# untitled.net
KiCad netlist of a schematic drawn in EAGLE
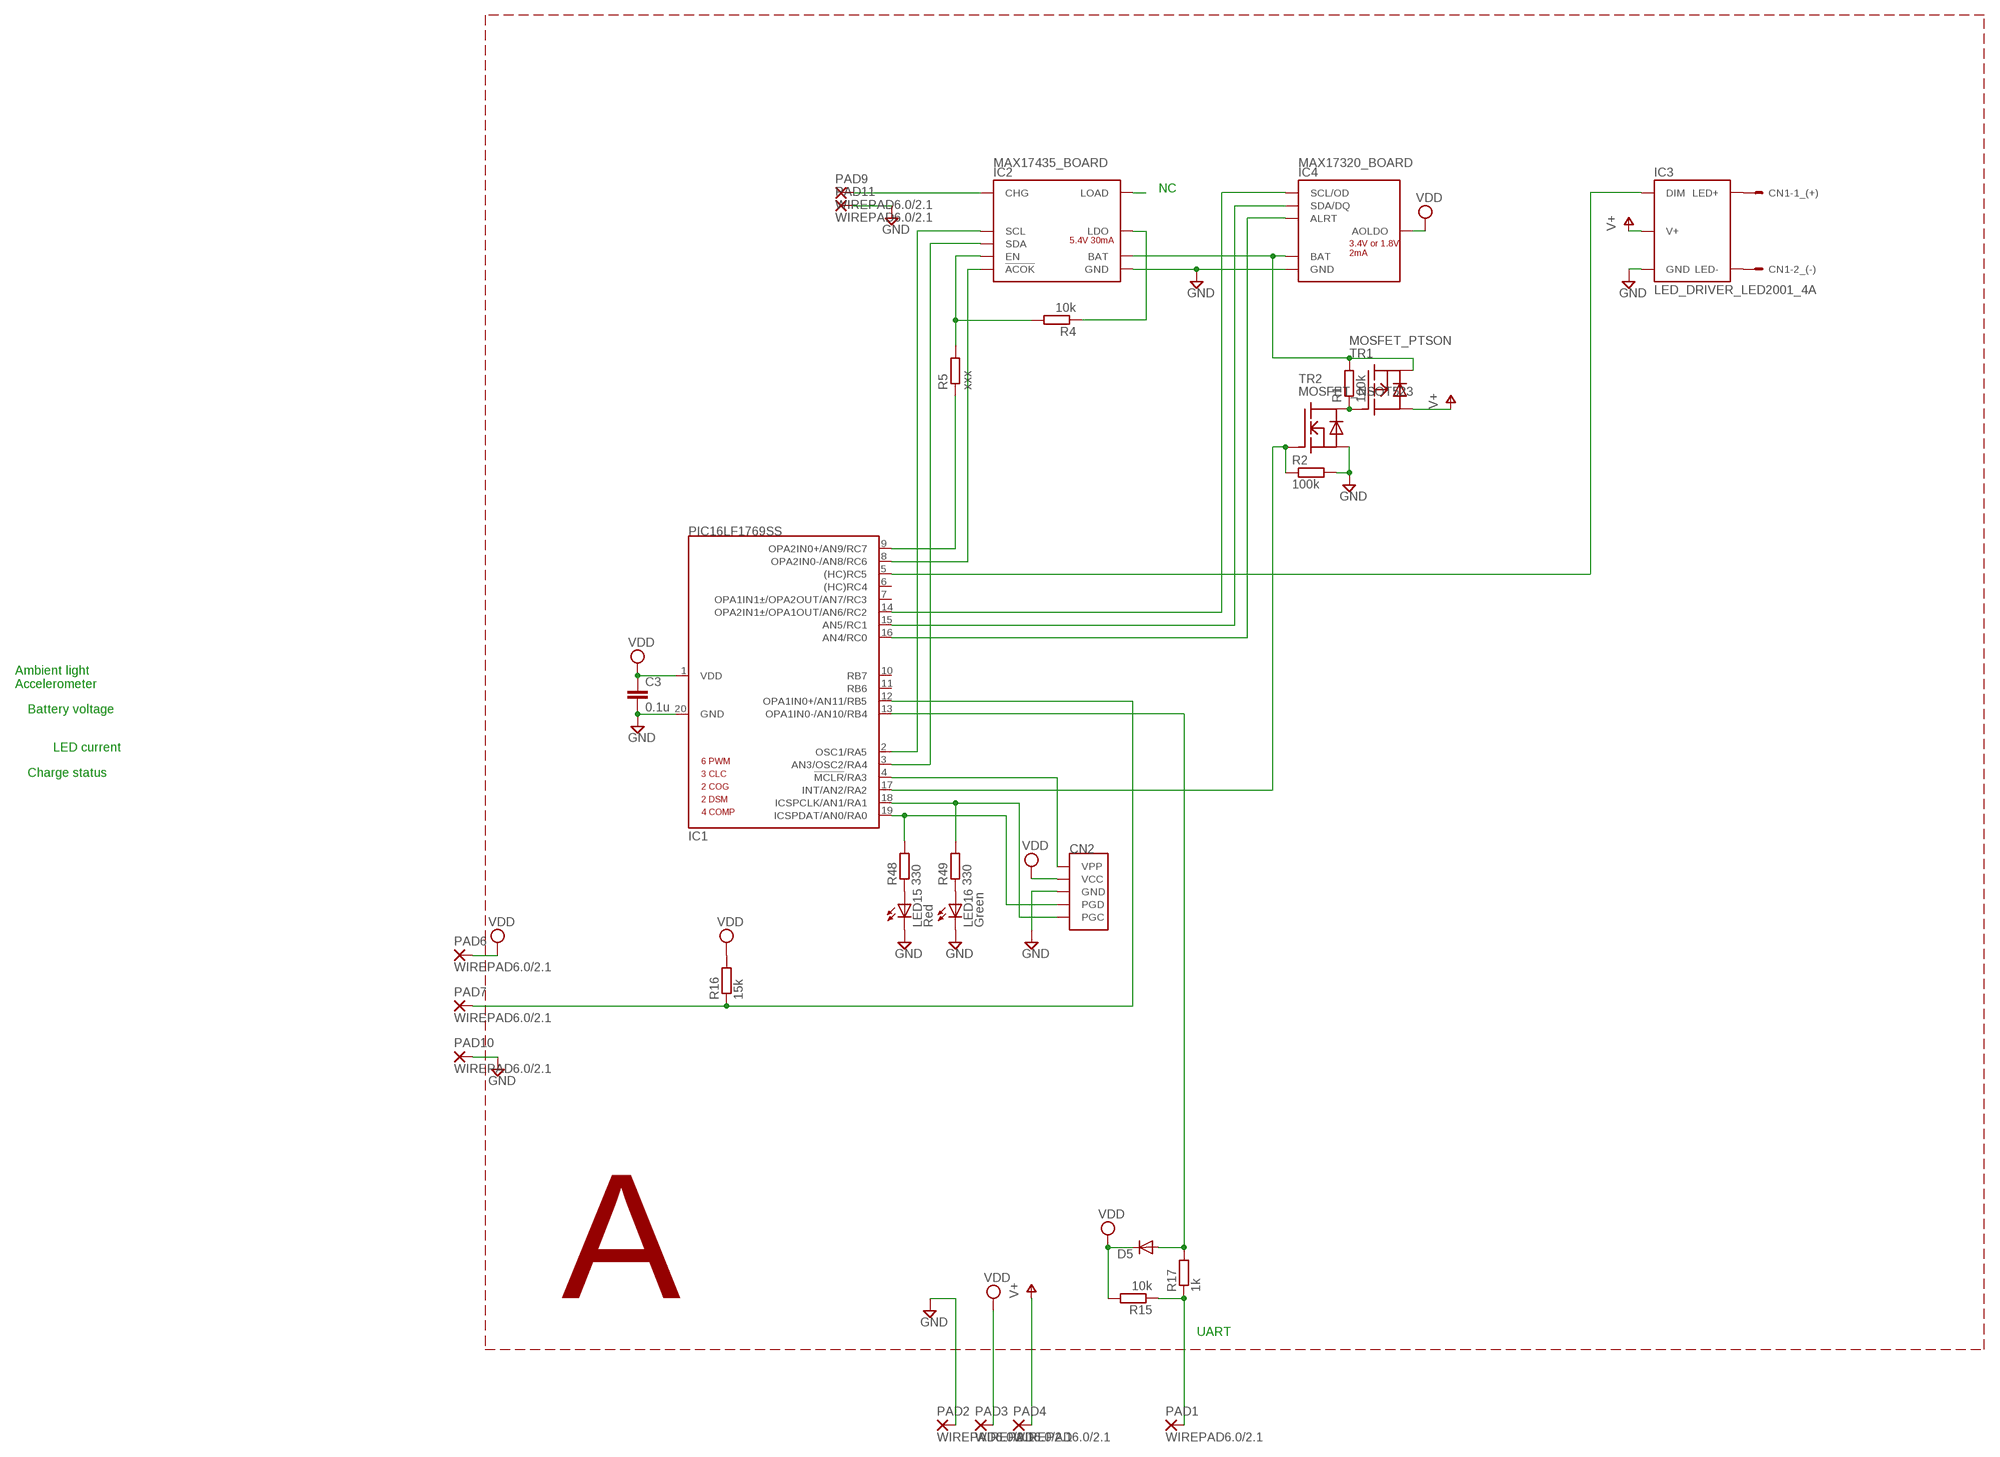
[diagram p0: schematic, sheet 1]

(export (version "E")
  (design (tool "Eeschema 10.0.6"))
  (components
    (comp (ref "C3")
      (value "0.1u")
      (footprint "eagle-import:C0402")
      (libsource (lib "eagle-import") (part "C-EUC0402"))
    )
    (comp (ref "CN1")
      (value "2P_(POWER)XH_S")
      (footprint "eagle-import:XH-2_S")
      (libsource (lib "eagle-import") (part "2P_(POWER)XH_S"))
    )
    (comp (ref "CN2")
      (value "ICSPEDGE")
      (footprint "eagle-import:MINI-ICSP_EDGE")
      (libsource (lib "eagle-import") (part "ICSPEDGE"))
    )
    (comp (ref "D5")
      (value "DIODE-VMN2")
      (footprint "eagle-import:VMN2")
      (libsource (lib "eagle-import") (part "DIODE-VMN2"))
    )
    (comp (ref "IC1")
      (value "PIC16LF1769SS")
      (footprint "eagle-import:SSOP20")
      (libsource (lib "eagle-import") (part "PIC16F1769SS"))
    )
    (comp (ref "IC2")
      (value "MAX17435_BOARD")
      (footprint "eagle-import:MAX17435_BOARD")
      (libsource (lib "eagle-import") (part "MAX17435_BOARD"))
    )
    (comp (ref "IC3")
      (value "LED_DRIVER_LED2001_4A")
      (footprint "eagle-import:LED_DRIVER_LED2001_4A")
      (libsource (lib "eagle-import") (part "LED_DRIVER_LED2001_4A"))
    )
    (comp (ref "IC4")
      (value "MAX17320_BOARD")
      (footprint "eagle-import:MAX17320_BOARD")
      (libsource (lib "eagle-import") (part "MAX17320_BOARD"))
    )
    (comp (ref "LED15")
      (value "Red")
      (footprint "eagle-import:CHIP-LED1606(SIDE)")
      (libsource (lib "eagle-import") (part "LEDCHIPLED_1606(SIDE)"))
    )
    (comp (ref "LED16")
      (value "Green")
      (footprint "eagle-import:CHIP-LED1606(SIDE)")
      (libsource (lib "eagle-import") (part "LEDCHIPLED_1606(SIDE)"))
    )
    (comp (ref "PAD1")
      (value "WIREPAD6.0/2.1")
      (footprint "eagle-import:6.0_2.1")
      (libsource (lib "eagle-import") (part "WIREPAD6.0/2.1"))
    )
    (comp (ref "PAD2")
      (value "WIREPAD6.0/2.1")
      (footprint "eagle-import:6.0_2.1")
      (libsource (lib "eagle-import") (part "WIREPAD6.0/2.1"))
    )
    (comp (ref "PAD3")
      (value "WIREPAD6.0/2.1")
      (footprint "eagle-import:6.0_2.1")
      (libsource (lib "eagle-import") (part "WIREPAD6.0/2.1"))
    )
    (comp (ref "PAD4")
      (value "WIREPAD6.0/2.1")
      (footprint "eagle-import:6.0_2.1")
      (libsource (lib "eagle-import") (part "WIREPAD6.0/2.1"))
    )
    (comp (ref "PAD6")
      (value "WIREPAD6.0/2.1")
      (footprint "eagle-import:6.0_2.1")
      (libsource (lib "eagle-import") (part "WIREPAD6.0/2.1"))
    )
    (comp (ref "PAD7")
      (value "WIREPAD6.0/2.1")
      (footprint "eagle-import:6.0_2.1")
      (libsource (lib "eagle-import") (part "WIREPAD6.0/2.1"))
    )
    (comp (ref "PAD9")
      (value "WIREPAD6.0/2.1")
      (footprint "eagle-import:6.0_2.1")
      (libsource (lib "eagle-import") (part "WIREPAD6.0/2.1"))
    )
    (comp (ref "PAD10")
      (value "WIREPAD6.0/2.1")
      (footprint "eagle-import:6.0_2.1")
      (libsource (lib "eagle-import") (part "WIREPAD6.0/2.1"))
    )
    (comp (ref "PAD11")
      (value "WIREPAD6.0/2.1")
      (footprint "eagle-import:6.0_2.1")
      (libsource (lib "eagle-import") (part "WIREPAD6.0/2.1"))
    )
    (comp (ref "R1")
      (value "100k")
      (footprint "eagle-import:R0402")
      (libsource (lib "eagle-import") (part "R-EU_R0402"))
    )
    (comp (ref "R2")
      (value "100k")
      (footprint "eagle-import:R0402")
      (libsource (lib "eagle-import") (part "R-EU_R0402"))
    )
    (comp (ref "R4")
      (value "10k")
      (footprint "eagle-import:R0402")
      (libsource (lib "eagle-import") (part "R-EU_R0402"))
    )
    (comp (ref "R5")
      (value "xxx")
      (footprint "eagle-import:R0402")
      (libsource (lib "eagle-import") (part "R-EU_R0402"))
    )
    (comp (ref "R15")
      (value "10k")
      (footprint "eagle-import:R0402")
      (libsource (lib "eagle-import") (part "R-EU_R0402"))
    )
    (comp (ref "R16")
      (value "15k")
      (footprint "eagle-import:R0402")
      (libsource (lib "eagle-import") (part "R-EU_R0402"))
    )
    (comp (ref "R17")
      (value "1k")
      (footprint "eagle-import:R0402")
      (libsource (lib "eagle-import") (part "R-EU_R0402"))
    )
    (comp (ref "R48")
      (value "330")
      (footprint "eagle-import:R0402")
      (libsource (lib "eagle-import") (part "R-EU_R0402"))
    )
    (comp (ref "R49")
      (value "330")
      (footprint "eagle-import:R0402")
      (libsource (lib "eagle-import") (part "R-EU_R0402"))
    )
    (comp (ref "TR1")
      (value "MOSFET_PTSON")
      (footprint "eagle-import:TSON_ADVANCE")
      (libsource (lib "eagle-import") (part "MOSFET_PTSON"))
    )
    (comp (ref "TR2")
      (value "MOSFET_NSOT523")
      (footprint "eagle-import:SOT523")
      (libsource (lib "eagle-import") (part "MOSFET_NSOT523"))
    )
  )
  (nets
    (net (code "1") (name "GND") (class "Default")
      (node (ref "C3") (pin "2") (pinfunction "2_2") (pintype "passive"))
      (node (ref "CN2") (pin "GND") (pinfunction "GND_GND") (pintype "power_in"))
      (node (ref "IC1") (pin "20") (pinfunction "GND_20") (pintype "power_in"))
      (node (ref "IC2") (pin "GND") (pinfunction "GND_GND") (pintype "power_in"))
      (node (ref "IC2") (pin "GND@1") (pinfunction "GND_GND@1") (pintype "power_in"))
      (node (ref "IC2") (pin "GND@2") (pinfunction "GND_GND@2") (pintype "power_in"))
      (node (ref "IC2") (pin "GND@3") (pinfunction "GND_GND@3") (pintype "power_in"))
      (node (ref "IC2") (pin "GND@4") (pinfunction "GND_GND@4") (pintype "power_in"))
      (node (ref "IC2") (pin "GND@5") (pinfunction "GND_GND@5") (pintype "power_in"))
      (node (ref "IC2") (pin "GND@6") (pinfunction "GND_GND@6") (pintype "power_in"))
      (node (ref "IC3") (pin "GND") (pinfunction "GND_GND") (pintype "power_in"))
      (node (ref "IC3") (pin "GND@1") (pinfunction "GND_GND@1") (pintype "power_in"))
      (node (ref "IC3") (pin "GND@2") (pinfunction "GND_GND@2") (pintype "power_in"))
      (node (ref "IC4") (pin "GND") (pinfunction "GND_GND") (pintype "power_in"))
      (node (ref "IC4") (pin "GND@1") (pinfunction "GND_GND@1") (pintype "power_in"))
      (node (ref "IC4") (pin "GND@2") (pinfunction "GND_GND@2") (pintype "power_in"))
      (node (ref "IC4") (pin "GND@3") (pinfunction "GND_GND@3") (pintype "power_in"))
      (node (ref "IC4") (pin "GND@4") (pinfunction "GND_GND@4") (pintype "power_in"))
      (node (ref "IC4") (pin "GND@5") (pinfunction "GND_GND@5") (pintype "power_in"))
      (node (ref "IC4") (pin "GND@6") (pinfunction "GND_GND@6") (pintype "power_in"))
      (node (ref "LED15") (pin "C") (pinfunction "C_C") (pintype "passive"))
      (node (ref "LED16") (pin "C") (pinfunction "C_C") (pintype "passive"))
      (node (ref "PAD10") (pin "1") (pinfunction "P_1") (pintype "passive"))
      (node (ref "PAD11") (pin "1") (pinfunction "P_1") (pintype "passive"))
      (node (ref "PAD2") (pin "1") (pinfunction "P_1") (pintype "passive"))
      (node (ref "R2") (pin "2") (pinfunction "2_2") (pintype "passive"))
      (node (ref "TR2") (pin "2") (pinfunction "S_2") (pintype "bidirectional"))
    )
    (net (code "2") (name "Net-(CN1A-S)") (class "Default")
      (node (ref "CN1") (pin "1") (pinfunction "S_1") (pintype "passive"))
      (node (ref "IC3") (pin "LED+") (pinfunction "LED+_LED+") (pintype "output"))
    )
    (net (code "3") (name "Net-(CN1B-S)") (class "Default")
      (node (ref "CN1") (pin "2") (pinfunction "S_2") (pintype "passive"))
      (node (ref "IC3") (pin "LED-") (pinfunction "LED-_LED-") (pintype "output"))
    )
    (net (code "4") (name "Net-(IC1-(HC)RC5)") (class "Default")
      (node (ref "IC1") (pin "5") (pinfunction "(HC)RC5_5") (pintype "bidirectional"))
      (node (ref "IC3") (pin "DIM") (pinfunction "DIM_DIM") (pintype "input"))
    )
    (net (code "5") (name "Net-(IC1-AN3{slash}OSC2{slash}RA4)") (class "Default")
      (node (ref "IC1") (pin "3") (pinfunction "AN3/OSC2/RA4_3") (pintype "bidirectional"))
      (node (ref "IC2") (pin "SDA") (pinfunction "SDA_SDA") (pintype "bidirectional"))
    )
    (net (code "6") (name "Net-(IC1-AN4{slash}RC0)") (class "Default")
      (node (ref "IC1") (pin "16") (pinfunction "AN4/RC0_16") (pintype "bidirectional"))
      (node (ref "IC4") (pin "ALRT") (pinfunction "ALRT_ALRT") (pintype "bidirectional"))
    )
    (net (code "7") (name "Net-(IC1-AN5{slash}RC1)") (class "Default")
      (node (ref "IC1") (pin "15") (pinfunction "AN5/RC1_15") (pintype "bidirectional"))
      (node (ref "IC4") (pin "SDA/DQ") (pinfunction "SDA/DQ_SDA/DQ") (pintype "bidirectional"))
    )
    (net (code "8") (name "Net-(IC1-ICSPCLK{slash}AN1{slash}RA1)") (class "Default")
      (node (ref "CN2") (pin "PGC") (pinfunction "PGC_PGC") (pintype "output"))
      (node (ref "IC1") (pin "18") (pinfunction "ICSPCLK/AN1/RA1_18") (pintype "bidirectional"))
      (node (ref "R49") (pin "2") (pinfunction "2_2") (pintype "passive"))
    )
    (net (code "9") (name "Net-(IC1-ICSPDAT{slash}AN0{slash}RA0)") (class "Default")
      (node (ref "CN2") (pin "PGD") (pinfunction "PGD_PGD") (pintype "bidirectional"))
      (node (ref "IC1") (pin "19") (pinfunction "ICSPDAT/AN0/RA0_19") (pintype "bidirectional"))
      (node (ref "R48") (pin "2") (pinfunction "2_2") (pintype "passive"))
    )
    (net (code "10") (name "Net-(IC1-INT{slash}AN2{slash}RA2)") (class "Default")
      (node (ref "IC1") (pin "17") (pinfunction "INT/AN2/RA2_17") (pintype "bidirectional"))
      (node (ref "R2") (pin "1") (pinfunction "1_1") (pintype "passive"))
      (node (ref "TR2") (pin "1") (pinfunction "G_1") (pintype "bidirectional"))
    )
    (net (code "11") (name "Net-(IC1-OPA1IN0+{slash}AN11{slash}RB5)") (class "Default")
      (node (ref "IC1") (pin "12") (pinfunction "OPA1IN0+/AN11/RB5_12") (pintype "bidirectional"))
      (node (ref "PAD7") (pin "1") (pinfunction "P_1") (pintype "passive"))
      (node (ref "R16") (pin "1") (pinfunction "1_1") (pintype "passive"))
    )
    (net (code "12") (name "Net-(IC1-OPA1IN0-{slash}AN10{slash}RB4)") (class "Default")
      (node (ref "D5") (pin "A") (pinfunction "A_A") (pintype "passive"))
      (node (ref "IC1") (pin "13") (pinfunction "OPA1IN0-/AN10/RB4_13") (pintype "bidirectional"))
      (node (ref "R17") (pin "2") (pinfunction "2_2") (pintype "passive"))
    )
    (net (code "13") (name "Net-(IC1-OPA2IN0+{slash}AN9{slash}RC7)") (class "Default")
      (node (ref "IC1") (pin "9") (pinfunction "OPA2IN0+/AN9/RC7_9") (pintype "bidirectional"))
      (node (ref "R5") (pin "1") (pinfunction "1_1") (pintype "passive"))
    )
    (net (code "14") (name "Net-(IC1-OPA2IN0-{slash}AN8{slash}RC6)") (class "Default")
      (node (ref "IC1") (pin "8") (pinfunction "OPA2IN0-/AN8/RC6_8") (pintype "bidirectional"))
      (node (ref "IC2") (pin "!ACOK") (pinfunction "~{ACOK}_!ACOK") (pintype "output"))
    )
    (net (code "15") (name "Net-(IC1-OPA2IN1±{slash}OPA1OUT{slash}AN6{slash}RC2)") (class "Default")
      (node (ref "IC1") (pin "14") (pinfunction "OPA2IN1±/OPA1OUT/AN6/RC2_14") (pintype "bidirectional"))
      (node (ref "IC4") (pin "SCL/OD") (pinfunction "SCL/OD_SCL/OD") (pintype "bidirectional"))
    )
    (net (code "16") (name "Net-(IC1-OSC1{slash}RA5)") (class "Default")
      (node (ref "IC1") (pin "2") (pinfunction "OSC1/RA5_2") (pintype "bidirectional"))
      (node (ref "IC2") (pin "SCL") (pinfunction "SCL_SCL") (pintype "bidirectional"))
    )
    (net (code "17") (name "Net-(IC1-~{MCLR}{slash}RA3)") (class "Default")
      (node (ref "CN2") (pin "VPP") (pinfunction "VPP_VPP") (pintype "output"))
      (node (ref "IC1") (pin "4") (pinfunction "~{MCLR}/RA3_4") (pintype "input"))
    )
    (net (code "18") (name "Net-(IC2-PadBAT)") (class "Default")
      (node (ref "IC2") (pin "BAT") (pinfunction "BAT_BAT") (pintype "bidirectional"))
      (node (ref "IC4") (pin "BAT") (pinfunction "BAT_BAT") (pintype "input"))
      (node (ref "IC4") (pin "BAT@1") (pinfunction "BAT_BAT@1") (pintype "input"))
      (node (ref "IC4") (pin "BAT@2") (pinfunction "BAT_BAT@2") (pintype "input"))
      (node (ref "R1") (pin "2") (pinfunction "2_2") (pintype "passive"))
      (node (ref "TR1") (pin "1") (pinfunction "S_1") (pintype "bidirectional"))
      (node (ref "TR1") (pin "2") (pinfunction "S_2") (pintype "bidirectional"))
      (node (ref "TR1") (pin "3") (pinfunction "S_3") (pintype "bidirectional"))
    )
    (net (code "19") (name "Net-(IC2-PadEN)") (class "Default")
      (node (ref "IC2") (pin "EN") (pinfunction "EN_EN") (pintype "input"))
      (node (ref "R4") (pin "2") (pinfunction "2_2") (pintype "passive"))
      (node (ref "R5") (pin "2") (pinfunction "2_2") (pintype "passive"))
    )
    (net (code "20") (name "Net-(IC2-PadLDO)") (class "Default")
      (node (ref "IC2") (pin "LDO") (pinfunction "LDO_LDO") (pintype "output"))
      (node (ref "R4") (pin "1") (pinfunction "1_1") (pintype "passive"))
    )
    (net (code "21") (name "Net-(LED15-PadA)") (class "Default")
      (node (ref "LED15") (pin "A") (pinfunction "A_A") (pintype "passive"))
      (node (ref "R48") (pin "1") (pinfunction "1_1") (pintype "passive"))
    )
    (net (code "22") (name "Net-(LED16-PadA)") (class "Default")
      (node (ref "LED16") (pin "A") (pinfunction "A_A") (pintype "passive"))
      (node (ref "R49") (pin "1") (pinfunction "1_1") (pintype "passive"))
    )
    (net (code "23") (name "Net-(PAD1-P)") (class "Default")
      (node (ref "PAD1") (pin "1") (pinfunction "P_1") (pintype "passive"))
      (node (ref "R15") (pin "1") (pinfunction "1_1") (pintype "passive"))
      (node (ref "R17") (pin "1") (pinfunction "1_1") (pintype "passive"))
    )
    (net (code "24") (name "Net-(PAD9-P)") (class "Default")
      (node (ref "IC2") (pin "CHG") (pinfunction "CHG_CHG") (pintype "input"))
      (node (ref "PAD9") (pin "1") (pinfunction "P_1") (pintype "passive"))
    )
    (net (code "25") (name "Net-(TR1-G)") (class "Default")
      (node (ref "R1") (pin "1") (pinfunction "1_1") (pintype "passive"))
      (node (ref "TR1") (pin "4") (pinfunction "G_4") (pintype "bidirectional"))
      (node (ref "TR2") (pin "3") (pinfunction "D_3") (pintype "bidirectional"))
    )
    (net (code "26") (name "V+") (class "Default")
      (node (ref "IC3") (pin "V+") (pinfunction "V+_V+") (pintype "power_in"))
      (node (ref "PAD4") (pin "1") (pinfunction "P_1") (pintype "passive"))
      (node (ref "TR1") (pin "5") (pinfunction "D_5") (pintype "bidirectional"))
      (node (ref "TR1") (pin "5_") (pinfunction "D_5_") (pintype "bidirectional"))
      (node (ref "TR1") (pin "6") (pinfunction "D_6") (pintype "bidirectional"))
      (node (ref "TR1") (pin "7") (pinfunction "D_7") (pintype "bidirectional"))
      (node (ref "TR1") (pin "8") (pinfunction "D_8") (pintype "bidirectional"))
      (node (ref "TR1") (pin "8_") (pinfunction "D_8_") (pintype "bidirectional"))
      (node (ref "TR1") (pin "EP") (pinfunction "D_EP") (pintype "bidirectional"))
      (node (ref "TR1") (pin "EP2") (pinfunction "D_EP2") (pintype "bidirectional"))
    )
    (net (code "27") (name "VDD") (class "Default")
      (node (ref "C3") (pin "1") (pinfunction "1_1") (pintype "passive"))
      (node (ref "CN2") (pin "VCC") (pinfunction "VCC_VCC") (pintype "power_in"))
      (node (ref "D5") (pin "C") (pinfunction "C_C") (pintype "passive"))
      (node (ref "IC1") (pin "1") (pinfunction "VDD_1") (pintype "power_in"))
      (node (ref "IC4") (pin "AOLDO") (pinfunction "AOLDO_AOLDO") (pintype "bidirectional"))
      (node (ref "PAD3") (pin "1") (pinfunction "P_1") (pintype "passive"))
      (node (ref "PAD6") (pin "1") (pinfunction "P_1") (pintype "passive"))
      (node (ref "R15") (pin "2") (pinfunction "2_2") (pintype "passive"))
      (node (ref "R16") (pin "2") (pinfunction "2_2") (pintype "passive"))
    )
    (net (code "28") (name "unconnected-(IC1-(HC)RC4-Pad6)") (class "Default")
      (node (ref "IC1") (pin "6") (pinfunction "(HC)RC4_6") (pintype "bidirectional"))
    )
    (net (code "29") (name "unconnected-(IC1-OPA1IN1±{slash}OPA2OUT{slash}AN7{slash}RC3-Pad7)") (class "Default")
      (node (ref "IC1") (pin "7") (pinfunction "OPA1IN1±/OPA2OUT/AN7/RC3_7") (pintype "bidirectional"))
    )
    (net (code "30") (name "unconnected-(IC1-RB6-Pad11)") (class "Default")
      (node (ref "IC1") (pin "11") (pinfunction "RB6_11") (pintype "bidirectional"))
    )
    (net (code "31") (name "unconnected-(IC1-RB7-Pad10)") (class "Default")
      (node (ref "IC1") (pin "10") (pinfunction "RB7_10") (pintype "bidirectional"))
    )
    (net (code "32") (name "unconnected-(IC2-PadLOAD)") (class "Default")
      (node (ref "IC2") (pin "LOAD") (pinfunction "LOAD_LOAD") (pintype "output"))
    )
  )
)
